# PX_PMIC.net
KiCad netlist of a schematic drawn in Altium Designer
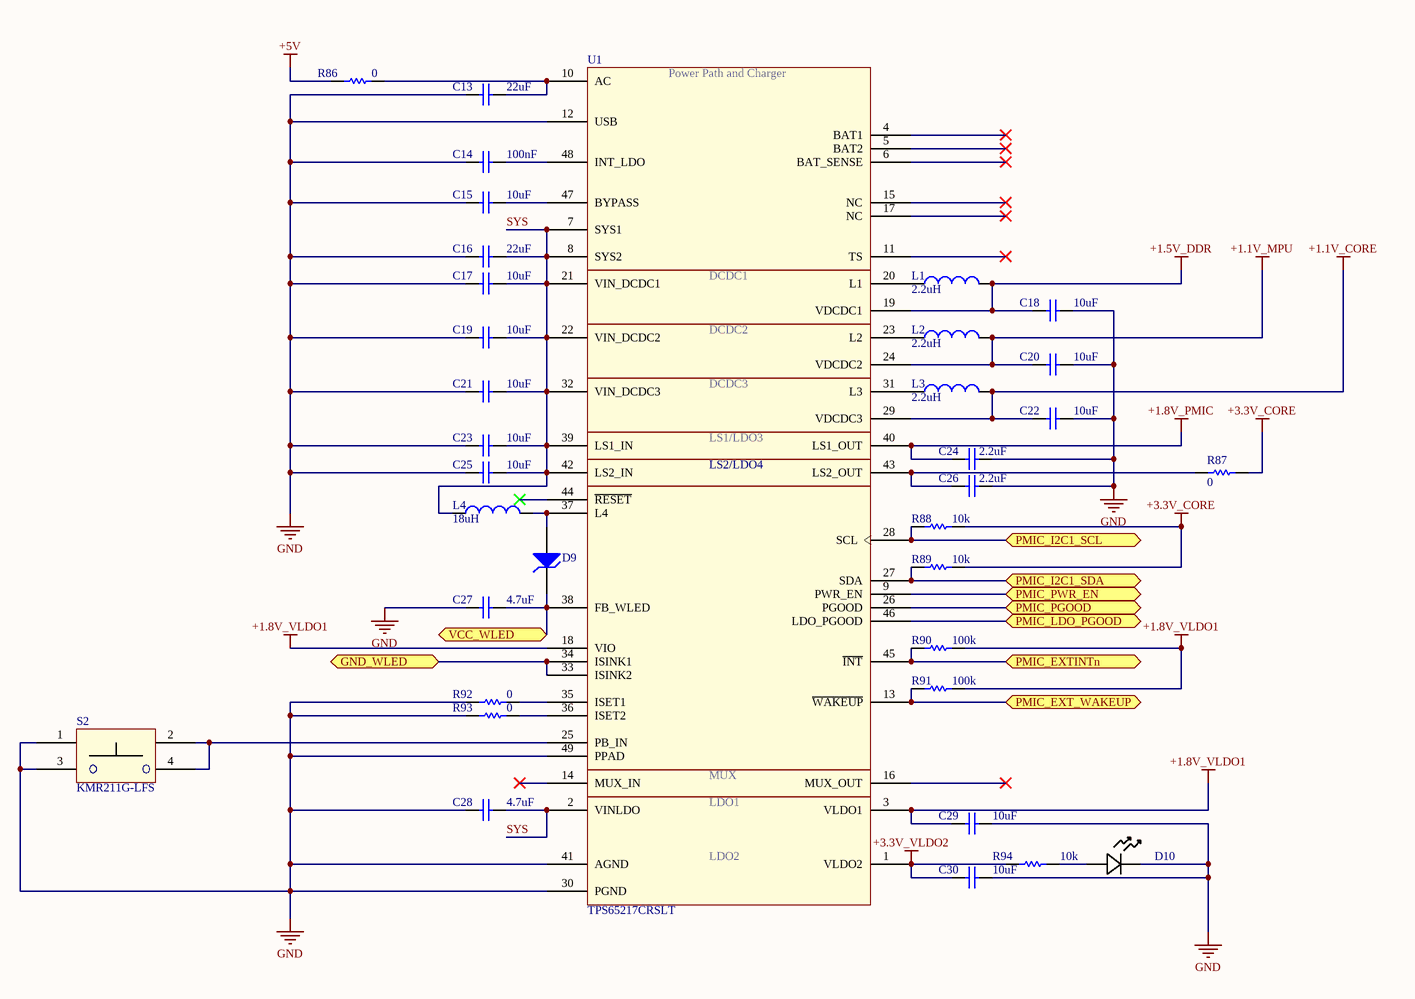
[diagram p0: PX_PMIC.SchDoc]

(export (version "E")
  (design (tool "Eeschema 10.0.6"))
  (components
    (comp (ref "C13")
      (value "22uF")
      (footprint "CAPC1608X08")
      (description "Capacitor")
      (fields (field (name "Comment") "Cap"))
      (libsource (lib "Michel") (part "Cap"))
    )
    (comp (ref "C14")
      (value "100nF")
      (footprint "CAPC1608X08")
      (description "Capacitor")
      (fields (field (name "Comment") "Cap"))
      (libsource (lib "Michel") (part "Cap"))
    )
    (comp (ref "C15")
      (value "10uF")
      (footprint "CAPC1608X08")
      (description "Capacitor")
      (fields (field (name "Comment") "Cap"))
      (libsource (lib "Michel") (part "Cap"))
    )
    (comp (ref "C16")
      (value "22uF")
      (footprint "CAPC1608X08")
      (description "Capacitor")
      (fields (field (name "Comment") "Cap"))
      (libsource (lib "Michel") (part "Cap"))
    )
    (comp (ref "C17")
      (value "10uF")
      (footprint "CAPC1608X08")
      (description "Capacitor")
      (fields (field (name "Comment") "Cap"))
      (libsource (lib "Michel") (part "Cap"))
    )
    (comp (ref "C18")
      (value "10uF")
      (footprint "CAPC1608X08")
      (description "Capacitor")
      (fields (field (name "Comment") "Cap"))
      (libsource (lib "Michel") (part "Cap"))
    )
    (comp (ref "C19")
      (value "10uF")
      (footprint "CAPC1608X08")
      (description "Capacitor")
      (fields (field (name "Comment") "Cap"))
      (libsource (lib "Michel") (part "Cap"))
    )
    (comp (ref "C20")
      (value "10uF")
      (footprint "CAPC1608X08")
      (description "Capacitor")
      (fields (field (name "Comment") "Cap"))
      (libsource (lib "Michel") (part "Cap"))
    )
    (comp (ref "C21")
      (value "10uF")
      (footprint "CAPC1608X08")
      (description "Capacitor")
      (fields (field (name "Comment") "Cap"))
      (libsource (lib "Michel") (part "Cap"))
    )
    (comp (ref "C22")
      (value "10uF")
      (footprint "CAPC1608X08")
      (description "Capacitor")
      (fields (field (name "Comment") "Cap"))
      (libsource (lib "Michel") (part "Cap"))
    )
    (comp (ref "C23")
      (value "10uF")
      (footprint "CAPC1608X08")
      (description "Capacitor")
      (fields (field (name "Comment") "Cap"))
      (libsource (lib "Michel") (part "Cap"))
    )
    (comp (ref "C24")
      (value "2.2uF")
      (footprint "CAPC1608X08")
      (description "Capacitor")
      (fields (field (name "Comment") "Cap"))
      (libsource (lib "Michel") (part "Cap"))
    )
    (comp (ref "C25")
      (value "10uF")
      (footprint "CAPC1608X08")
      (description "Capacitor")
      (fields (field (name "Comment") "Cap"))
      (libsource (lib "Michel") (part "Cap"))
    )
    (comp (ref "C26")
      (value "2.2uF")
      (footprint "CAPC1608X08")
      (description "Capacitor")
      (fields (field (name "Comment") "Cap"))
      (libsource (lib "Michel") (part "Cap"))
    )
    (comp (ref "C27")
      (value "4.7uF")
      (footprint "CAPC1608X08")
      (description "Capacitor")
      (fields (field (name "Comment") "Cap"))
      (libsource (lib "Michel") (part "Cap"))
    )
    (comp (ref "C28")
      (value "4.7uF")
      (footprint "CAPC1608X08")
      (description "Capacitor")
      (fields (field (name "Comment") "Cap"))
      (libsource (lib "Michel") (part "Cap"))
    )
    (comp (ref "C29")
      (value "10uF")
      (footprint "CAPC1608X08")
      (description "Capacitor")
      (fields (field (name "Comment") "Cap"))
      (libsource (lib "Michel") (part "Cap"))
    )
    (comp (ref "C30")
      (value "10uF")
      (footprint "CAPC1608X08")
      (description "Capacitor")
      (fields (field (name "Comment") "Cap"))
      (libsource (lib "Michel") (part "Cap"))
    )
    (comp (ref "D9")
      (value "D Zener")
      (footprint "MF03A-M")
      (description "Zener Diode")
      (libsource (lib "Michel") (part "D Zener"))
    )
    (comp (ref "D10")
      (value "Blanc")
      (footprint "LED_LNJ")
      (description "LED Blanc")
      (libsource (lib "Michel") (part "LNJ037X8ARA"))
    )
    (comp (ref "L1")
      (value "2.2uH")
      (footprint "INDM1608X08N")
      (description "Inductor")
      (libsource (lib "Michel") (part "Inductor"))
    )
    (comp (ref "L2")
      (value "2.2uH")
      (footprint "INDM1608X08N")
      (description "Inductor")
      (libsource (lib "Michel") (part "Inductor"))
    )
    (comp (ref "L3")
      (value "2.2uH")
      (footprint "INDM1608X08N")
      (description "Inductor")
      (libsource (lib "Michel") (part "Inductor"))
    )
    (comp (ref "L4")
      (value "18uH")
      (footprint "INDM2612X12N")
      (description "Inductor")
      (libsource (lib "Michel") (part "Inductor"))
    )
    (comp (ref "R86")
      (value "0")
      (footprint "RESC1608X05")
      (description "Resistor")
      (fields (field (name "Comment") "Res1"))
      (libsource (lib "Michel") (part "Res1"))
    )
    (comp (ref "R87")
      (value "0")
      (footprint "RESC1608X05")
      (description "Resistor")
      (fields (field (name "Comment") "Res1"))
      (libsource (lib "Michel") (part "Res1"))
    )
    (comp (ref "R88")
      (value "10k")
      (footprint "RESC1608X05")
      (description "Resistor")
      (fields (field (name "Comment") "Res1"))
      (libsource (lib "Michel") (part "Res1"))
    )
    (comp (ref "R89")
      (value "10k")
      (footprint "RESC1608X05")
      (description "Resistor")
      (fields (field (name "Comment") "Res1"))
      (libsource (lib "Michel") (part "Res1"))
    )
    (comp (ref "R90")
      (value "100k")
      (footprint "RESC1608X05")
      (description "Resistor")
      (fields (field (name "Comment") "Res1"))
      (libsource (lib "Michel") (part "Res1"))
    )
    (comp (ref "R91")
      (value "100k")
      (footprint "RESC1608X05")
      (description "Resistor")
      (fields (field (name "Comment") "Res1"))
      (libsource (lib "Michel") (part "Res1"))
    )
    (comp (ref "R92")
      (value "0")
      (footprint "RESC1608X05")
      (description "Resistor")
      (fields (field (name "Comment") "Res1"))
      (libsource (lib "Michel") (part "Res1"))
    )
    (comp (ref "R93")
      (value "0")
      (footprint "RESC1608X05")
      (description "Resistor")
      (fields (field (name "Comment") "Res1"))
      (libsource (lib "Michel") (part "Res1"))
    )
    (comp (ref "R94")
      (value "10k")
      (footprint "RESC1608X05")
      (description "Resistor")
      (fields (field (name "Comment") "Res1"))
      (libsource (lib "Michel") (part "Res1"))
    )
    (comp (ref "S2")
      (value "KMR211G-LFS")
      (footprint "C&K_KMR211G")
      (description "Commutateur tactile")
      (libsource (lib "Michel") (part "KMR211G-LFS"))
    )
    (comp (ref "U1")
      (value "TPS65217CRSLT")
      (footprint "CRSLT")
      (description "Gestion d'alimentation PMIC")
      (libsource (lib "Michel") (part "TPS65217CRSLT"))
    )
  )
  (nets
    (net (code "1") (name "+1.1V_CORE") (class "Default")
      (node (ref "C22") (pin "1") (pinfunction "1_1") (pintype "passive"))
      (node (ref "L3") (pin "2") (pinfunction "2_2") (pintype "passive"))
      (node (ref "U1") (pin "29") (pinfunction "VDCDC3_29") (pintype "passive"))
    )
    (net (code "2") (name "+1.1V_MPU") (class "Default")
      (node (ref "C20") (pin "1") (pinfunction "1_1") (pintype "passive"))
      (node (ref "L2") (pin "2") (pinfunction "2_2") (pintype "passive"))
      (node (ref "U1") (pin "24") (pinfunction "VDCDC2_24") (pintype "passive"))
    )
    (net (code "3") (name "+1.5V_DDR") (class "Default")
      (node (ref "C18") (pin "1") (pinfunction "1_1") (pintype "passive"))
      (node (ref "L1") (pin "2") (pinfunction "2_2") (pintype "passive"))
      (node (ref "U1") (pin "19") (pinfunction "VDCDC1_19") (pintype "passive"))
    )
    (net (code "4") (name "+1.8V_PMIC") (class "Default")
      (node (ref "C24") (pin "2") (pinfunction "2_2") (pintype "passive"))
      (node (ref "U1") (pin "40") (pinfunction "LS1_OUT_40") (pintype "passive"))
    )
    (net (code "5") (name "+1.8V_VLDO1") (class "Default")
      (node (ref "C29") (pin "1") (pinfunction "1_1") (pintype "passive"))
      (node (ref "R90") (pin "2") (pinfunction "2_2") (pintype "passive"))
      (node (ref "R91") (pin "2") (pinfunction "2_2") (pintype "passive"))
      (node (ref "U1") (pin "18") (pinfunction "VIO_18") (pintype "passive"))
      (node (ref "U1") (pin "3") (pinfunction "VLDO1_3") (pintype "passive"))
    )
    (net (code "6") (name "+3.3V_CORE") (class "Default")
      (node (ref "R87") (pin "1") (pinfunction "1_1") (pintype "passive"))
      (node (ref "R88") (pin "2") (pinfunction "2_2") (pintype "passive"))
      (node (ref "R89") (pin "2") (pinfunction "2_2") (pintype "passive"))
    )
    (net (code "7") (name "+3.3V_VLDO2") (class "Default")
      (node (ref "C30") (pin "1") (pinfunction "1_1") (pintype "passive"))
      (node (ref "R94") (pin "1") (pinfunction "1_1") (pintype "passive"))
      (node (ref "U1") (pin "1") (pinfunction "VLDO2_1") (pintype "passive"))
    )
    (net (code "8") (name "+5V") (class "Default")
      (node (ref "R86") (pin "1") (pinfunction "1_1") (pintype "passive"))
    )
    (net (code "9") (name "/GND_WLED") (class "Default")
      (node (ref "U1") (pin "33") (pinfunction "ISINK2_33") (pintype "passive"))
      (node (ref "U1") (pin "34") (pinfunction "ISINK1_34") (pintype "passive"))
    )
    (net (code "10") (name "/PMIC_EXTINTn") (class "Default")
      (node (ref "R90") (pin "1") (pinfunction "1_1") (pintype "passive"))
      (node (ref "U1") (pin "45") (pinfunction "~{INT}_45") (pintype "passive"))
    )
    (net (code "11") (name "/PMIC_EXT_WAKEUP") (class "Default")
      (node (ref "R91") (pin "1") (pinfunction "1_1") (pintype "passive"))
      (node (ref "U1") (pin "13") (pinfunction "~{WAKEUP}_13") (pintype "passive"))
    )
    (net (code "12") (name "/PMIC_I2C1_SCL") (class "Default")
      (node (ref "R88") (pin "1") (pinfunction "1_1") (pintype "passive"))
      (node (ref "U1") (pin "28") (pinfunction "SCL_28") (pintype "passive"))
    )
    (net (code "13") (name "/PMIC_I2C1_SDA") (class "Default")
      (node (ref "R89") (pin "1") (pinfunction "1_1") (pintype "passive"))
      (node (ref "U1") (pin "27") (pinfunction "SDA_27") (pintype "passive"))
    )
    (net (code "14") (name "/PMIC_LDO_PGOOD") (class "Default")
      (node (ref "U1") (pin "46") (pinfunction "LDO_PGOOD_46") (pintype "passive"))
    )
    (net (code "15") (name "/PMIC_PGOOD") (class "Default")
      (node (ref "U1") (pin "26") (pinfunction "PGOOD_26") (pintype "passive"))
    )
    (net (code "16") (name "/PMIC_PWR_EN") (class "Default")
      (node (ref "U1") (pin "9") (pinfunction "PWR_EN_9") (pintype "passive"))
    )
    (net (code "17") (name "/SYS") (class "Default")
      (node (ref "C16") (pin "2") (pinfunction "2_2") (pintype "passive"))
      (node (ref "C17") (pin "2") (pinfunction "2_2") (pintype "passive"))
      (node (ref "C19") (pin "2") (pinfunction "2_2") (pintype "passive"))
      (node (ref "C21") (pin "2") (pinfunction "2_2") (pintype "passive"))
      (node (ref "C23") (pin "2") (pinfunction "2_2") (pintype "passive"))
      (node (ref "C25") (pin "2") (pinfunction "2_2") (pintype "passive"))
      (node (ref "C28") (pin "2") (pinfunction "2_2") (pintype "passive"))
      (node (ref "L4") (pin "1") (pinfunction "1_1") (pintype "passive"))
      (node (ref "U1") (pin "2") (pinfunction "VINLDO_2") (pintype "passive"))
      (node (ref "U1") (pin "21") (pinfunction "VIN_DCDC1_21") (pintype "passive"))
      (node (ref "U1") (pin "22") (pinfunction "VIN_DCDC2_22") (pintype "passive"))
      (node (ref "U1") (pin "32") (pinfunction "VIN_DCDC3_32") (pintype "passive"))
      (node (ref "U1") (pin "39") (pinfunction "LS1_IN_39") (pintype "passive"))
      (node (ref "U1") (pin "42") (pinfunction "LS2_IN_42") (pintype "passive"))
      (node (ref "U1") (pin "7") (pinfunction "SYS1_7") (pintype "passive"))
      (node (ref "U1") (pin "8") (pinfunction "SYS2_8") (pintype "passive"))
    )
    (net (code "18") (name "/VCC_WLED") (class "Default")
      (node (ref "C27") (pin "2") (pinfunction "2_2") (pintype "passive"))
      (node (ref "D9") (pin "2") (pinfunction "K_2") (pintype "passive"))
      (node (ref "U1") (pin "38") (pinfunction "FB_WLED_38") (pintype "passive"))
    )
    (net (code "19") (name "GND") (class "Default")
      (node (ref "C13") (pin "1") (pinfunction "1_1") (pintype "passive"))
      (node (ref "C14") (pin "1") (pinfunction "1_1") (pintype "passive"))
      (node (ref "C15") (pin "1") (pinfunction "1_1") (pintype "passive"))
      (node (ref "C16") (pin "1") (pinfunction "1_1") (pintype "passive"))
      (node (ref "C17") (pin "1") (pinfunction "1_1") (pintype "passive"))
      (node (ref "C18") (pin "2") (pinfunction "2_2") (pintype "passive"))
      (node (ref "C19") (pin "1") (pinfunction "1_1") (pintype "passive"))
      (node (ref "C20") (pin "2") (pinfunction "2_2") (pintype "passive"))
      (node (ref "C21") (pin "1") (pinfunction "1_1") (pintype "passive"))
      (node (ref "C22") (pin "2") (pinfunction "2_2") (pintype "passive"))
      (node (ref "C23") (pin "1") (pinfunction "1_1") (pintype "passive"))
      (node (ref "C24") (pin "1") (pinfunction "1_1") (pintype "passive"))
      (node (ref "C25") (pin "1") (pinfunction "1_1") (pintype "passive"))
      (node (ref "C26") (pin "1") (pinfunction "1_1") (pintype "passive"))
      (node (ref "C27") (pin "1") (pinfunction "1_1") (pintype "passive"))
      (node (ref "C28") (pin "1") (pinfunction "1_1") (pintype "passive"))
      (node (ref "C29") (pin "2") (pinfunction "2_2") (pintype "passive"))
      (node (ref "C30") (pin "2") (pinfunction "2_2") (pintype "passive"))
      (node (ref "D10") (pin "1") (pinfunction "1_1") (pintype "passive"))
      (node (ref "R92") (pin "1") (pinfunction "1_1") (pintype "passive"))
      (node (ref "R93") (pin "1") (pinfunction "1_1") (pintype "passive"))
      (node (ref "S2") (pin "1") (pinfunction "1_1") (pintype "passive"))
      (node (ref "S2") (pin "3") (pinfunction "3_3") (pintype "passive"))
      (node (ref "U1") (pin "12") (pinfunction "USB_12") (pintype "passive"))
      (node (ref "U1") (pin "30") (pinfunction "PGND_30") (pintype "passive"))
      (node (ref "U1") (pin "41") (pinfunction "AGND_41") (pintype "passive"))
      (node (ref "U1") (pin "49") (pinfunction "PPAD_49") (pintype "passive"))
    )
    (net (code "20") (name "Net-(D9-A)") (class "Default")
      (node (ref "D9") (pin "1") (pinfunction "A_1") (pintype "passive"))
      (node (ref "L4") (pin "2") (pinfunction "2_2") (pintype "passive"))
      (node (ref "U1") (pin "37") (pinfunction "L4_37") (pintype "passive"))
    )
    (net (code "21") (name "Net-(D10-Pad2)") (class "Default")
      (node (ref "D10") (pin "2") (pinfunction "2_2") (pintype "passive"))
      (node (ref "R94") (pin "2") (pinfunction "2_2") (pintype "passive"))
    )
    (net (code "22") (name "Net-(U1-AC)") (class "Default")
      (node (ref "C13") (pin "2") (pinfunction "2_2") (pintype "passive"))
      (node (ref "R86") (pin "2") (pinfunction "2_2") (pintype "passive"))
      (node (ref "U1") (pin "10") (pinfunction "AC_10") (pintype "passive"))
    )
    (net (code "23") (name "Net-(U1-BYPASS)") (class "Default")
      (node (ref "C15") (pin "2") (pinfunction "2_2") (pintype "passive"))
      (node (ref "U1") (pin "47") (pinfunction "BYPASS_47") (pintype "passive"))
    )
    (net (code "24") (name "Net-(U1-INT_LDO)") (class "Default")
      (node (ref "C14") (pin "2") (pinfunction "2_2") (pintype "passive"))
      (node (ref "U1") (pin "48") (pinfunction "INT_LDO_48") (pintype "passive"))
    )
    (net (code "25") (name "Net-(U1-ISET1)") (class "Default")
      (node (ref "R92") (pin "2") (pinfunction "2_2") (pintype "passive"))
      (node (ref "U1") (pin "35") (pinfunction "ISET1_35") (pintype "passive"))
    )
    (net (code "26") (name "Net-(U1-ISET2)") (class "Default")
      (node (ref "R93") (pin "2") (pinfunction "2_2") (pintype "passive"))
      (node (ref "U1") (pin "36") (pinfunction "ISET2_36") (pintype "passive"))
    )
    (net (code "27") (name "Net-(U1-L1)") (class "Default")
      (node (ref "L1") (pin "1") (pinfunction "1_1") (pintype "passive"))
      (node (ref "U1") (pin "20") (pinfunction "L1_20") (pintype "passive"))
    )
    (net (code "28") (name "Net-(U1-L2)") (class "Default")
      (node (ref "L2") (pin "1") (pinfunction "1_1") (pintype "passive"))
      (node (ref "U1") (pin "23") (pinfunction "L2_23") (pintype "passive"))
    )
    (net (code "29") (name "Net-(U1-L3)") (class "Default")
      (node (ref "L3") (pin "1") (pinfunction "1_1") (pintype "passive"))
      (node (ref "U1") (pin "31") (pinfunction "L3_31") (pintype "passive"))
    )
    (net (code "30") (name "Net-(U1-LS2_OUT)") (class "Default")
      (node (ref "C26") (pin "2") (pinfunction "2_2") (pintype "passive"))
      (node (ref "R87") (pin "2") (pinfunction "2_2") (pintype "passive"))
      (node (ref "U1") (pin "43") (pinfunction "LS2_OUT_43") (pintype "passive"))
    )
    (net (code "31") (name "Net-(U1-PB_IN)") (class "Default")
      (node (ref "S2") (pin "2") (pinfunction "2_2") (pintype "passive"))
      (node (ref "S2") (pin "4") (pinfunction "4_4") (pintype "passive"))
      (node (ref "U1") (pin "25") (pinfunction "PB_IN_25") (pintype "passive"))
    )
    (net (code "32") (name "unconnected-(U1-BAT1-Pad4)") (class "Default")
      (node (ref "U1") (pin "4") (pinfunction "BAT1_4") (pintype "passive+no_connect"))
    )
    (net (code "33") (name "unconnected-(U1-BAT2-Pad5)") (class "Default")
      (node (ref "U1") (pin "5") (pinfunction "BAT2_5") (pintype "passive+no_connect"))
    )
    (net (code "34") (name "unconnected-(U1-BAT_SENSE-Pad6)") (class "Default")
      (node (ref "U1") (pin "6") (pinfunction "BAT_SENSE_6") (pintype "passive+no_connect"))
    )
    (net (code "35") (name "unconnected-(U1-MUX_IN-Pad14)") (class "Default")
      (node (ref "U1") (pin "14") (pinfunction "MUX_IN_14") (pintype "passive+no_connect"))
    )
    (net (code "36") (name "unconnected-(U1-MUX_OUT-Pad16)") (class "Default")
      (node (ref "U1") (pin "16") (pinfunction "MUX_OUT_16") (pintype "passive+no_connect"))
    )
    (net (code "37") (name "unconnected-(U1-NC-Pad15)") (class "Default")
      (node (ref "U1") (pin "15") (pinfunction "NC_15") (pintype "passive+no_connect"))
    )
    (net (code "38") (name "unconnected-(U1-NC-Pad17)") (class "Default")
      (node (ref "U1") (pin "17") (pinfunction "NC_17") (pintype "passive+no_connect"))
    )
    (net (code "39") (name "unconnected-(U1-TS-Pad11)") (class "Default")
      (node (ref "U1") (pin "11") (pinfunction "TS_11") (pintype "passive+no_connect"))
    )
    (net (code "40") (name "unconnected-(U1-~{RESET}-Pad44)") (class "Default")
      (node (ref "U1") (pin "44") (pinfunction "~{RESET}_44") (pintype "passive+no_connect"))
    )
  )
)
